# Adafruit_LTC4316.net
KiCad netlist of a schematic drawn in EAGLE
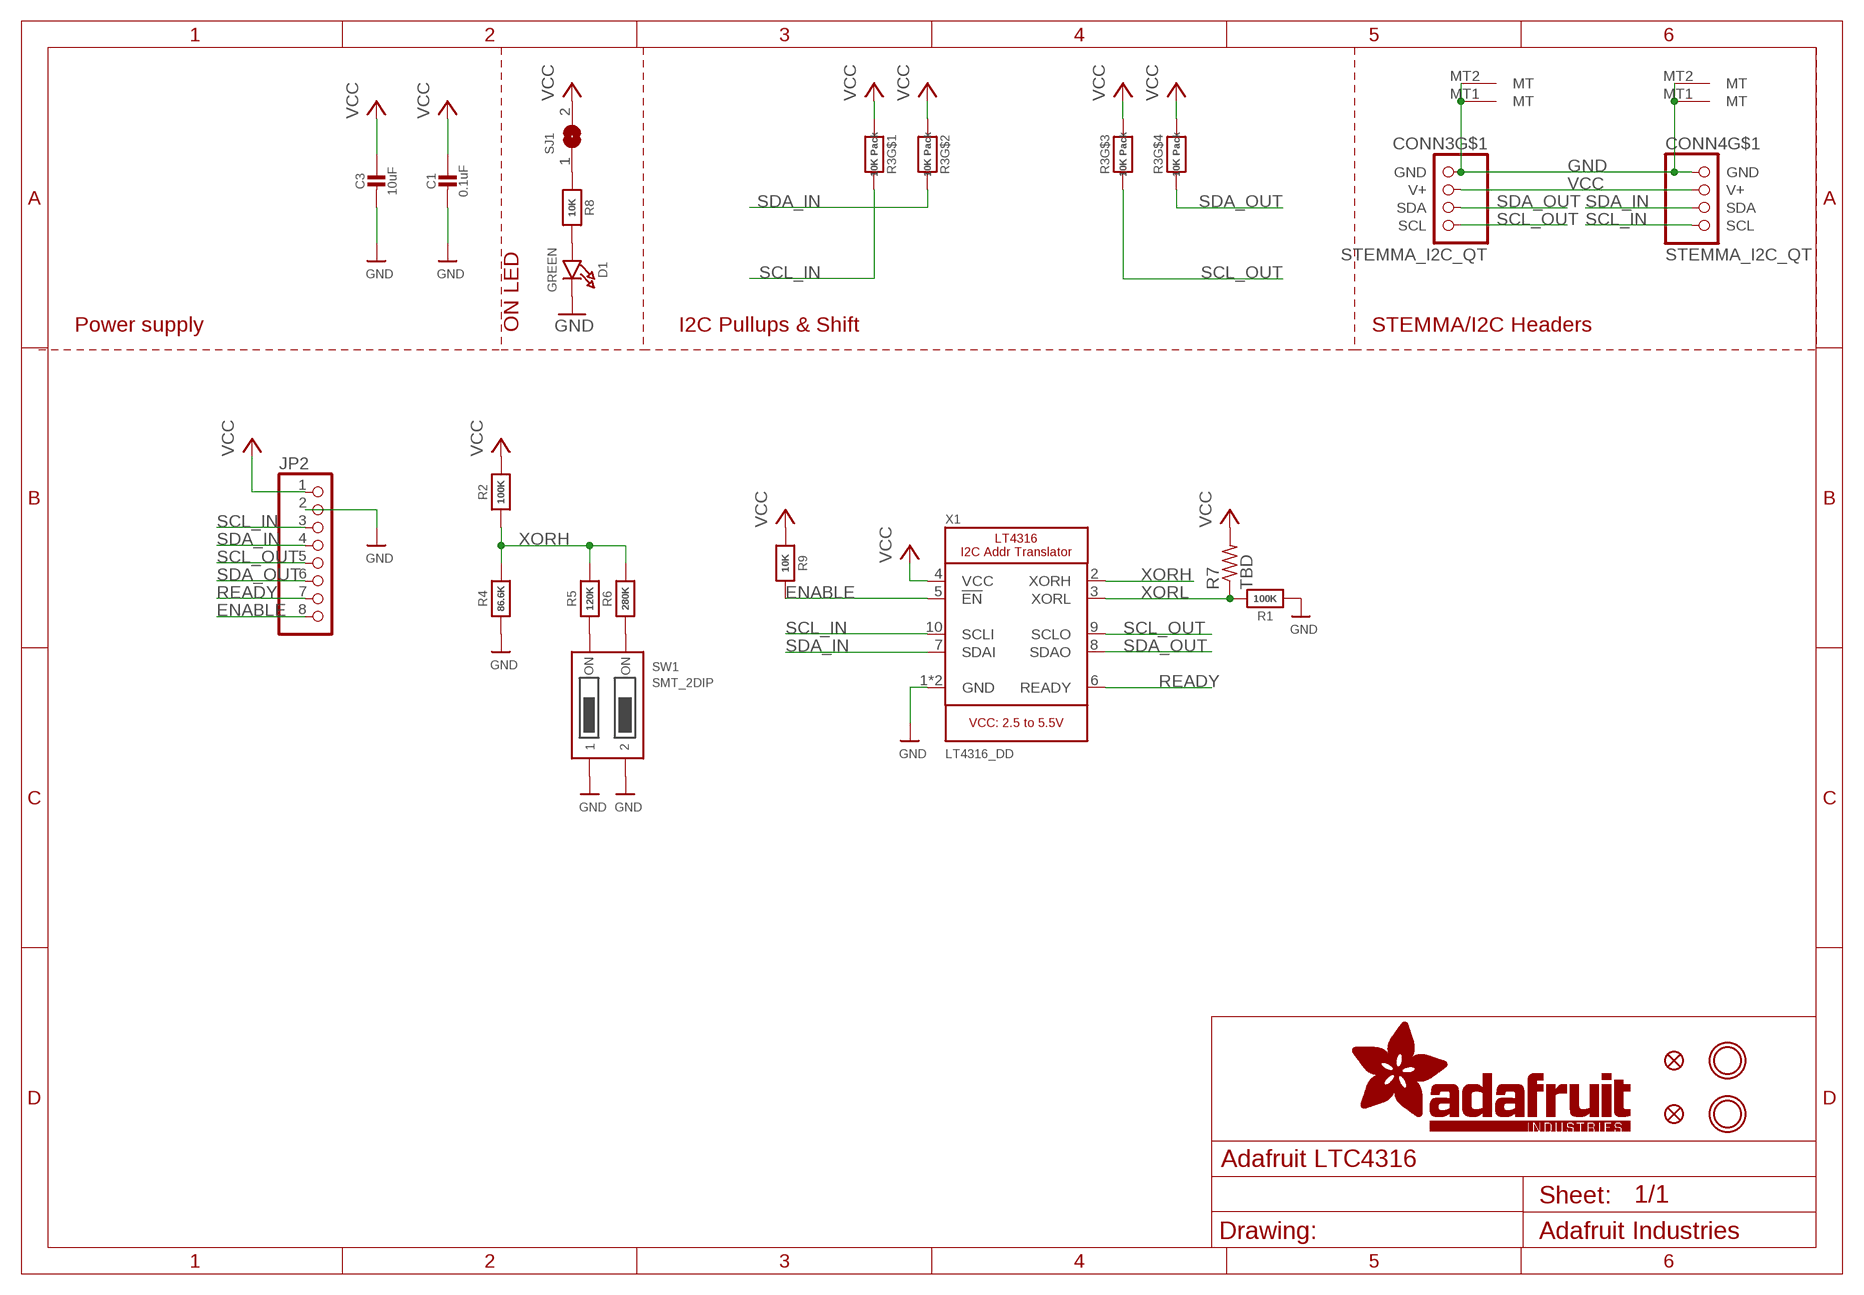
[diagram p0: schematic, sheet 1]

(export (version "E")
  (design (tool "Eeschema 10.0.6"))
  (components
    (comp (ref "C1")
      (value "0.1uF")
      (footprint "eagle-import:0603-NO")
      (libsource (lib "eagle-import") (part "CAP_CERAMIC0603_NO"))
    )
    (comp (ref "C3")
      (value "10uF")
      (footprint "eagle-import:0805-NO")
      (libsource (lib "eagle-import") (part "CAP_CERAMIC0805-NOOUTLINE"))
    )
    (comp (ref "CONN3")
      (value "STEMMA_I2C_QT")
      (footprint "eagle-import:JST_SH4")
      (libsource (lib "eagle-import") (part "STEMMA_I2C_QT"))
    )
    (comp (ref "CONN4")
      (value "STEMMA_I2C_QT")
      (footprint "eagle-import:JST_SH4")
      (libsource (lib "eagle-import") (part "STEMMA_I2C_QT"))
    )
    (comp (ref "D1")
      (value "GREEN")
      (footprint "eagle-import:CHIPLED_0603_NOOUTLINE")
      (libsource (lib "eagle-import") (part "LED0603_NOOUTLINE"))
    )
    (comp (ref "FID3")
      (value "FIDUCIAL_1MM")
      (footprint "eagle-import:FIDUCIAL_1MM")
      (libsource (lib "eagle-import") (part "FIDUCIAL_1MM"))
    )
    (comp (ref "FID4")
      (value "FIDUCIAL_1MM")
      (footprint "eagle-import:FIDUCIAL_1MM")
      (libsource (lib "eagle-import") (part "FIDUCIAL_1MM"))
    )
    (comp (ref "JP2")
      (value "HEADER-1X870MIL")
      (footprint "eagle-import:1X08_ROUND_70")
      (libsource (lib "eagle-import") (part "HEADER-1X870MIL"))
    )
    (comp (ref "R1")
      (value "100K")
      (footprint "eagle-import:0603-NO")
      (libsource (lib "eagle-import") (part "RESISTOR_0603_NOOUT"))
    )
    (comp (ref "R2")
      (value "100K")
      (footprint "eagle-import:0603-NO")
      (libsource (lib "eagle-import") (part "RESISTOR_0603_NOOUT"))
    )
    (comp (ref "R3")
      (value "10K Pack")
      (footprint "eagle-import:RESPACK_4X0603")
      (libsource (lib "eagle-import") (part "RESISTOR_4PACK"))
    )
    (comp (ref "R4")
      (value "86.6K")
      (footprint "eagle-import:0603-NO")
      (libsource (lib "eagle-import") (part "RESISTOR_0603_NOOUT"))
    )
    (comp (ref "R5")
      (value "120K")
      (footprint "eagle-import:0603-NO")
      (libsource (lib "eagle-import") (part "RESISTOR_0603_NOOUT"))
    )
    (comp (ref "R6")
      (value "280K")
      (footprint "eagle-import:0603-NO")
      (libsource (lib "eagle-import") (part "RESISTOR_0603_NOOUT"))
    )
    (comp (ref "R7")
      (value "TBD")
      (footprint "eagle-import:0204_7")
      (libsource (lib "eagle-import") (part "R-US_0204/7"))
    )
    (comp (ref "R8")
      (value "10K")
      (footprint "eagle-import:0603-NO")
      (libsource (lib "eagle-import") (part "RESISTOR_0603_NOOUT"))
    )
    (comp (ref "R9")
      (value "10K")
      (footprint "eagle-import:0603-NO")
      (libsource (lib "eagle-import") (part "RESISTOR_0603_NOOUT"))
    )
    (comp (ref "SJ1")
      (value "SOLDERJUMPERCLOSED")
      (footprint "eagle-import:SOLDERJUMPER_CLOSEDWIRE")
      (libsource (lib "eagle-import") (part "SOLDERJUMPERCLOSED"))
    )
    (comp (ref "SW1")
      (value "SMT_2DIP")
      (footprint "eagle-import:DIPSWITCH_2PIN")
      (libsource (lib "eagle-import") (part "DIPSWITCH_2PIN"))
    )
    (comp (ref "U$1")
      (value "MOUNTINGHOLE2.5")
      (footprint "eagle-import:MOUNTINGHOLE_2.5_PLATED")
      (libsource (lib "eagle-import") (part "MOUNTINGHOLE2.5"))
    )
    (comp (ref "U$17")
      (value "MOUNTINGHOLE2.5")
      (footprint "eagle-import:MOUNTINGHOLE_2.5_PLATED")
      (libsource (lib "eagle-import") (part "MOUNTINGHOLE2.5"))
    )
    (comp (ref "X1")
      (value "LT4316_DD")
      (footprint "eagle-import:DFN10_3X3MM")
      (libsource (lib "eagle-import") (part "LT4316_DD"))
    )
  )
  (nets
    (net (code "1") (name "/ENABLE") (class "Default")
      (node (ref "JP2") (pin "8") (pinfunction "8_8") (pintype "passive"))
      (node (ref "R9") (pin "2") (pinfunction "2_2") (pintype "passive"))
      (node (ref "X1") (pin "5") (pinfunction "~{EN}_5") (pintype "input"))
    )
    (net (code "2") (name "/READY") (class "Default")
      (node (ref "JP2") (pin "7") (pinfunction "7_7") (pintype "passive"))
      (node (ref "X1") (pin "6") (pinfunction "READY_6") (pintype "output"))
    )
    (net (code "3") (name "/SCL_IN") (class "Default")
      (node (ref "CONN4") (pin "4") (pinfunction "SCL_4") (pintype "passive"))
      (node (ref "JP2") (pin "3") (pinfunction "3_3") (pintype "passive"))
      (node (ref "R3") (pin "8") (pinfunction "2_8") (pintype "passive"))
      (node (ref "X1") (pin "10") (pinfunction "SCLI_10") (pintype "bidirectional"))
    )
    (net (code "4") (name "/SCL_OUT") (class "Default")
      (node (ref "CONN3") (pin "4") (pinfunction "SCL_4") (pintype "passive"))
      (node (ref "JP2") (pin "5") (pinfunction "5_5") (pintype "passive"))
      (node (ref "R3") (pin "3") (pinfunction "1_3") (pintype "passive"))
      (node (ref "X1") (pin "9") (pinfunction "SCLO_9") (pintype "bidirectional"))
    )
    (net (code "5") (name "/SDA_IN") (class "Default")
      (node (ref "CONN4") (pin "3") (pinfunction "SDA_3") (pintype "passive"))
      (node (ref "JP2") (pin "4") (pinfunction "4_4") (pintype "passive"))
      (node (ref "R3") (pin "7") (pinfunction "2_7") (pintype "passive"))
      (node (ref "X1") (pin "7") (pinfunction "SDAI_7") (pintype "bidirectional"))
    )
    (net (code "6") (name "/SDA_OUT") (class "Default")
      (node (ref "CONN3") (pin "3") (pinfunction "SDA_3") (pintype "passive"))
      (node (ref "JP2") (pin "6") (pinfunction "6_6") (pintype "passive"))
      (node (ref "R3") (pin "4") (pinfunction "1_4") (pintype "passive"))
      (node (ref "X1") (pin "8") (pinfunction "SDAO_8") (pintype "bidirectional"))
    )
    (net (code "7") (name "/XORH") (class "Default")
      (node (ref "R2") (pin "1") (pinfunction "1_1") (pintype "passive"))
      (node (ref "R4") (pin "2") (pinfunction "2_2") (pintype "passive"))
      (node (ref "R5") (pin "2") (pinfunction "2_2") (pintype "passive"))
      (node (ref "R6") (pin "2") (pinfunction "2_2") (pintype "passive"))
      (node (ref "X1") (pin "2") (pinfunction "XORH_2") (pintype "input"))
    )
    (net (code "8") (name "/XORL") (class "Default")
      (node (ref "R1") (pin "2") (pinfunction "2_2") (pintype "passive"))
      (node (ref "R7") (pin "1") (pinfunction "1_1") (pintype "passive"))
      (node (ref "X1") (pin "3") (pinfunction "XORL_3") (pintype "input"))
    )
    (net (code "9") (name "GND") (class "Default")
      (node (ref "C1") (pin "2") (pinfunction "2_2") (pintype "passive"))
      (node (ref "C3") (pin "2") (pinfunction "2_2") (pintype "passive"))
      (node (ref "CONN3") (pin "1") (pinfunction "GND_1") (pintype "passive"))
      (node (ref "CONN3") (pin "MT1") (pinfunction "MT_MT1") (pintype "bidirectional"))
      (node (ref "CONN3") (pin "MT2") (pinfunction "MT_MT2") (pintype "bidirectional"))
      (node (ref "CONN4") (pin "1") (pinfunction "GND_1") (pintype "passive"))
      (node (ref "CONN4") (pin "MT1") (pinfunction "MT_MT1") (pintype "bidirectional"))
      (node (ref "CONN4") (pin "MT2") (pinfunction "MT_MT2") (pintype "bidirectional"))
      (node (ref "D1") (pin "C") (pinfunction "C_C") (pintype "passive"))
      (node (ref "JP2") (pin "2") (pinfunction "2_2") (pintype "passive"))
      (node (ref "R1") (pin "1") (pinfunction "1_1") (pintype "passive"))
      (node (ref "R4") (pin "1") (pinfunction "1_1") (pintype "passive"))
      (node (ref "SW1") (pin "1OFF") (pinfunction "1OFF_1OFF") (pintype "bidirectional"))
      (node (ref "SW1") (pin "2OFF") (pinfunction "2OFF_2OFF") (pintype "bidirectional"))
      (node (ref "X1") (pin "1") (pinfunction "GND_1") (pintype "power_in"))
      (node (ref "X1") (pin "GND") (pinfunction "GND_GND") (pintype "power_in"))
    )
    (net (code "10") (name "Net-(D1-PadA)") (class "Default")
      (node (ref "D1") (pin "A") (pinfunction "A_A") (pintype "passive"))
      (node (ref "R8") (pin "2") (pinfunction "2_2") (pintype "passive"))
    )
    (net (code "11") (name "Net-(R5-Pad1)") (class "Default")
      (node (ref "R5") (pin "1") (pinfunction "1_1") (pintype "passive"))
      (node (ref "SW1") (pin "1ON") (pinfunction "1ON_1ON") (pintype "bidirectional"))
    )
    (net (code "12") (name "Net-(R6-Pad1)") (class "Default")
      (node (ref "R6") (pin "1") (pinfunction "1_1") (pintype "passive"))
      (node (ref "SW1") (pin "2ON") (pinfunction "2ON_2ON") (pintype "bidirectional"))
    )
    (net (code "13") (name "Net-(R8-Pad1)") (class "Default")
      (node (ref "R8") (pin "1") (pinfunction "1_1") (pintype "passive"))
      (node (ref "SJ1") (pin "1") (pinfunction "1_1") (pintype "passive"))
    )
    (net (code "14") (name "VCC") (class "Default")
      (node (ref "C1") (pin "1") (pinfunction "1_1") (pintype "passive"))
      (node (ref "C3") (pin "1") (pinfunction "1_1") (pintype "passive"))
      (node (ref "CONN3") (pin "2") (pinfunction "V+_2") (pintype "passive"))
      (node (ref "CONN4") (pin "2") (pinfunction "V+_2") (pintype "passive"))
      (node (ref "JP2") (pin "1") (pinfunction "1_1") (pintype "passive"))
      (node (ref "R2") (pin "2") (pinfunction "2_2") (pintype "passive"))
      (node (ref "R3") (pin "1") (pinfunction "1_1") (pintype "passive"))
      (node (ref "R3") (pin "2") (pinfunction "1_2") (pintype "passive"))
      (node (ref "R3") (pin "5") (pinfunction "2_5") (pintype "passive"))
      (node (ref "R3") (pin "6") (pinfunction "2_6") (pintype "passive"))
      (node (ref "R7") (pin "2") (pinfunction "2_2") (pintype "passive"))
      (node (ref "R9") (pin "1") (pinfunction "1_1") (pintype "passive"))
      (node (ref "SJ1") (pin "2") (pinfunction "2_2") (pintype "passive"))
      (node (ref "X1") (pin "4") (pinfunction "VCC_4") (pintype "power_in"))
    )
  )
)
